# schematic.net
KiCad netlist of a schematic drawn in EasyEDA
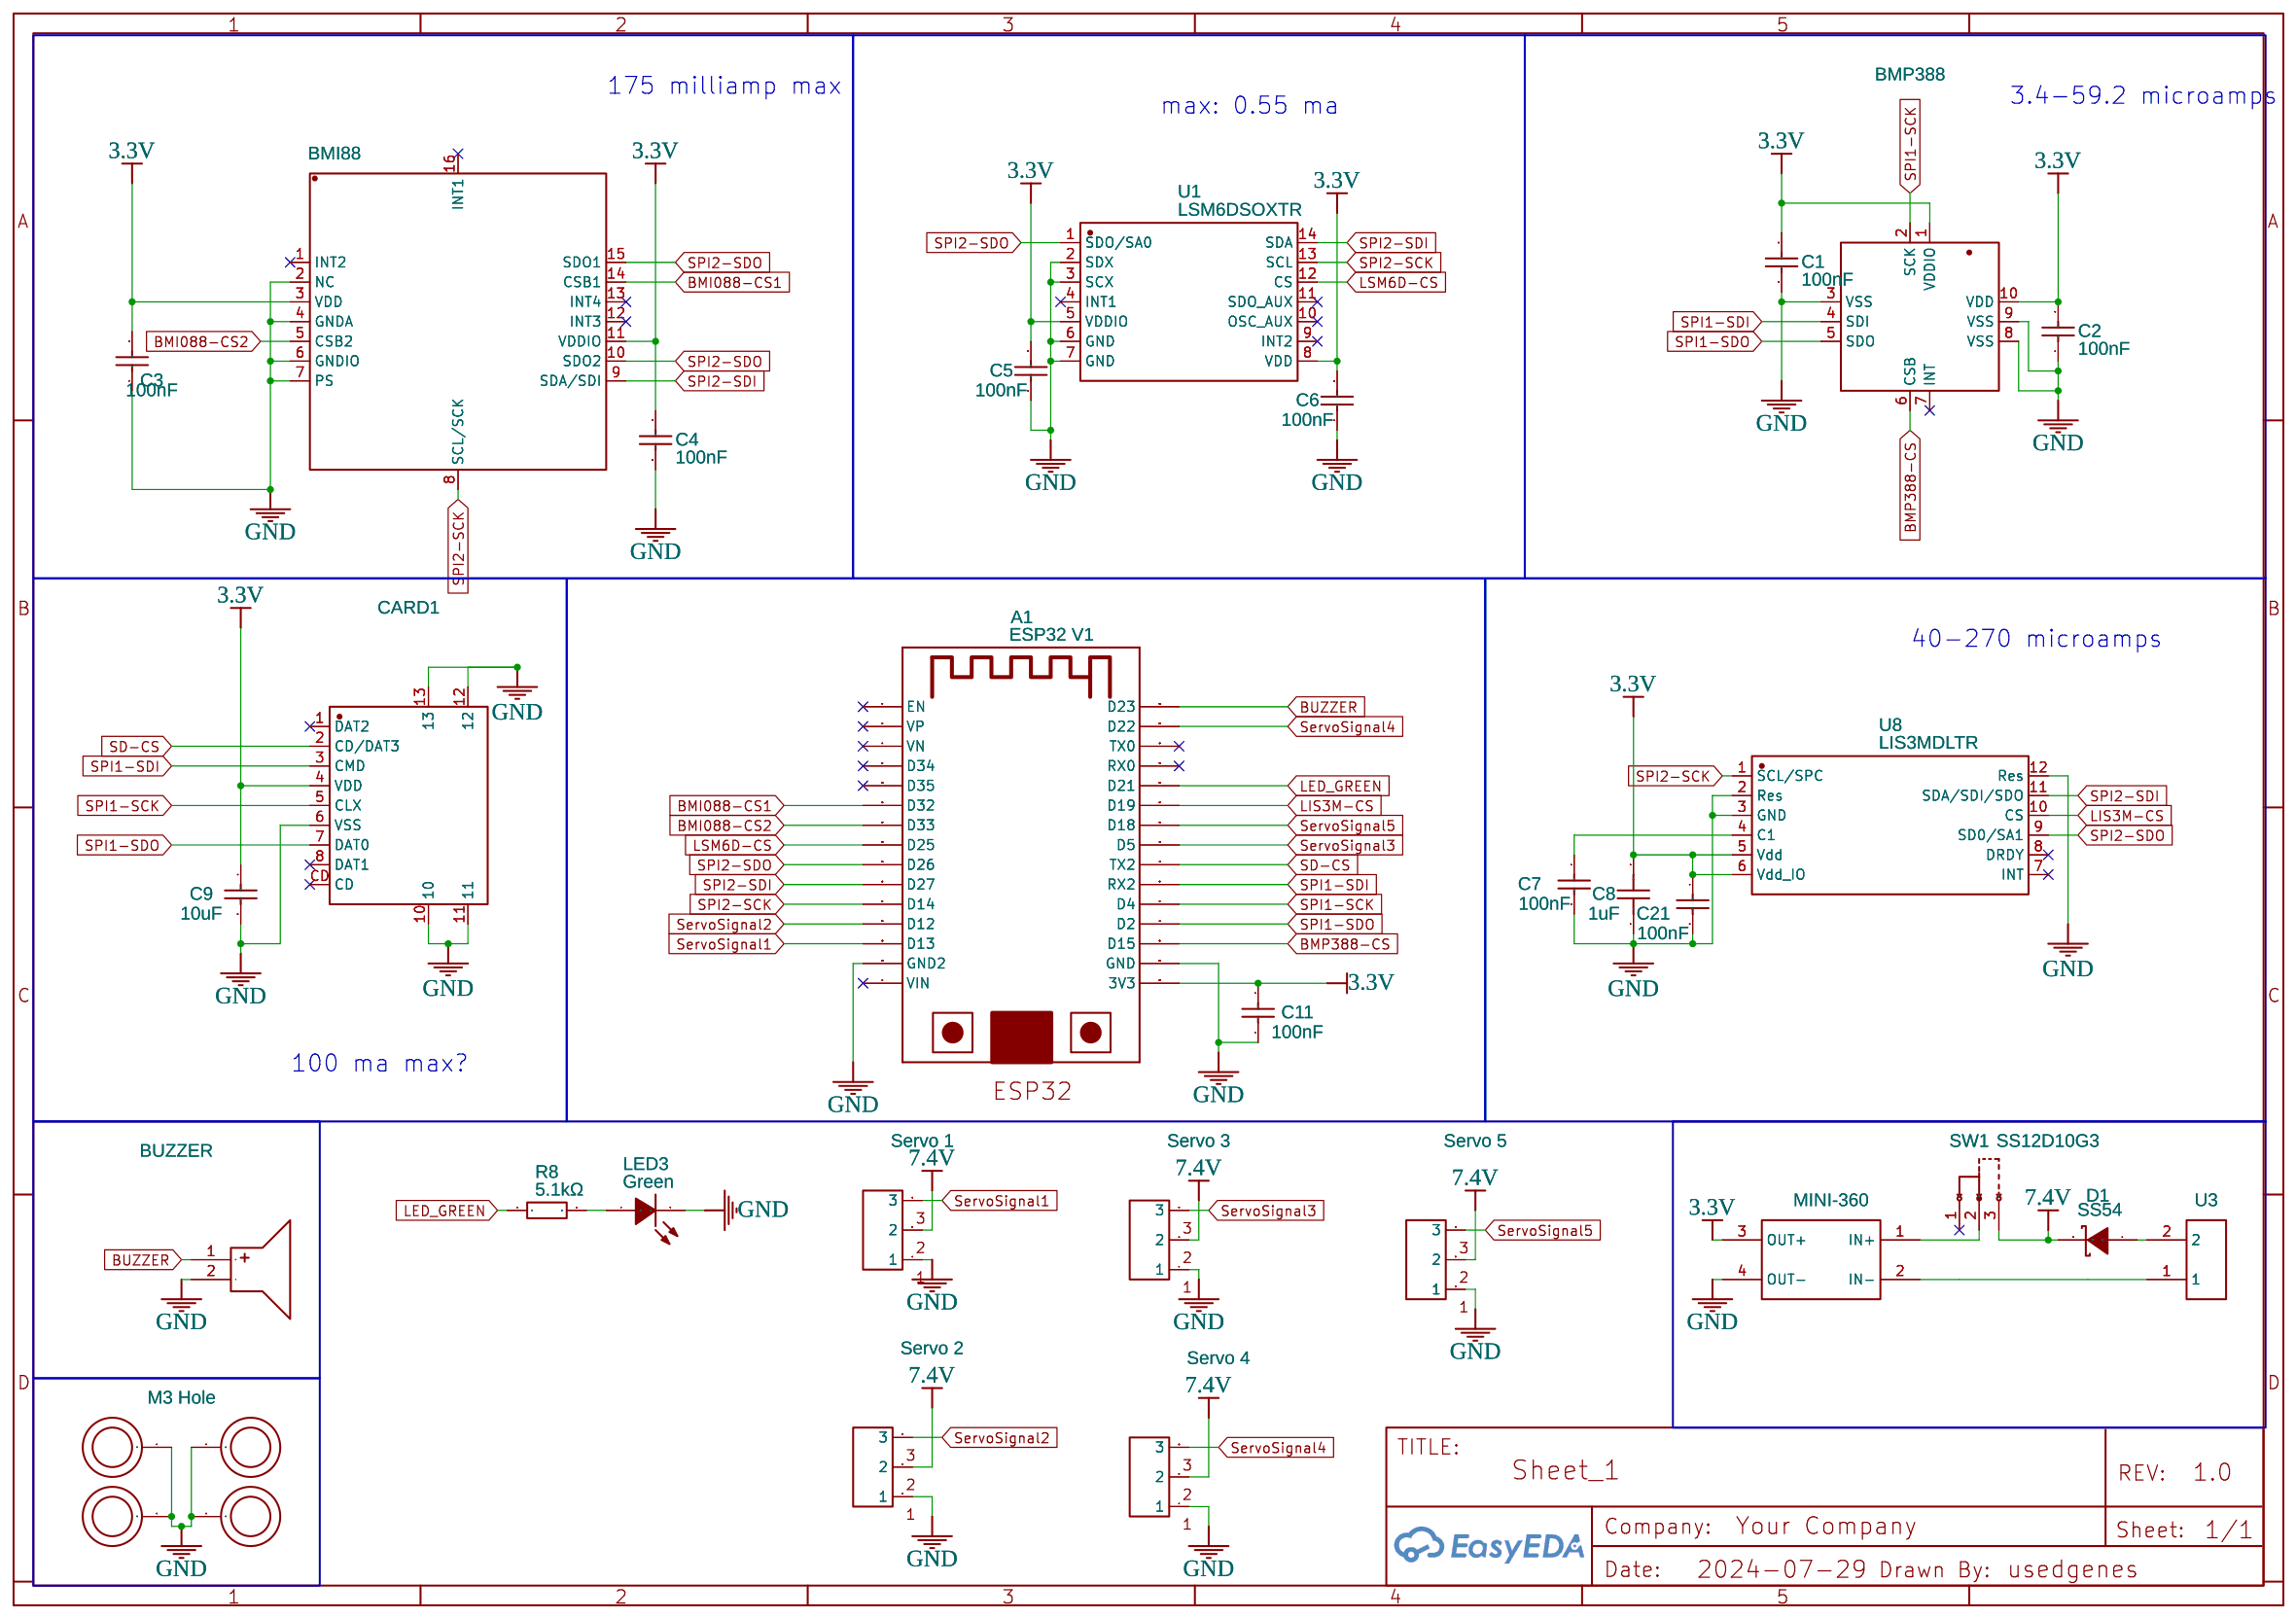
[diagram p0: schematic sheet]

(export (version "E")
  (design (tool "Eeschema 10.0.6"))
  (components
    (comp (ref "A1") (value "ESP32 V1") (libsource (lib "") (part "ESP32-DEVKIT-V1-30PIN")))
    (comp (ref "BMI88")
      (value "BMI088")
      (fields (field (name "Manufacturer") "Bosch(博世)"))
      (libsource (lib "") (part "BMI088"))
    )
    (comp (ref "BMP388")
      (value "BMP388")
      (fields (field (name "Manufacturer") "Bosch(博世)"))
      (libsource (lib "") (part "BMP388"))
    )
    (comp (ref "BUZZER")
      (value "4000Hz")
      (fields
        (field (name "Manufacturer Part") "SKY-1475-0540-45P7.6")
        (field (name "Manufacturer") "S&S(海旭)")
      )
      (libsource (lib "") (part "SKY-1475-0540-45P7.6"))
    )
    (comp (ref "C1")
      (value "100nF")
      (fields
        (field (name "Manufacturer Part") "CL05B104KO5NNNC")
        (field (name "Manufacturer") "SAMSUNG(三星)")
      )
      (libsource (lib "") (part "CL05B104KO5NNNC_1"))
    )
    (comp (ref "C2")
      (value "100nF")
      (fields
        (field (name "Manufacturer Part") "CL05B104KO5NNNC")
        (field (name "Manufacturer") "SAMSUNG(三星)")
      )
      (libsource (lib "") (part "CL05B104KO5NNNC_1"))
    )
    (comp (ref "C3")
      (value "100nF")
      (fields
        (field (name "Manufacturer Part") "CL05B104KO5NNNC")
        (field (name "Manufacturer") "SAMSUNG(三星)")
      )
      (libsource (lib "") (part "CL05B104KO5NNNC_1"))
    )
    (comp (ref "C4")
      (value "100nF")
      (fields
        (field (name "Manufacturer Part") "CL05B104KO5NNNC")
        (field (name "Manufacturer") "SAMSUNG(三星)")
      )
      (libsource (lib "") (part "CL05B104KO5NNNC_1"))
    )
    (comp (ref "C5")
      (value "100nF")
      (fields
        (field (name "Manufacturer Part") "CL05B104KO5NNNC")
        (field (name "Manufacturer") "SAMSUNG(三星)")
      )
      (libsource (lib "") (part "CL05B104KO5NNNC_1"))
    )
    (comp (ref "C6")
      (value "100nF")
      (fields
        (field (name "Manufacturer Part") "CL05B104KO5NNNC")
        (field (name "Manufacturer") "SAMSUNG(三星)")
      )
      (libsource (lib "") (part "CL05B104KO5NNNC_1"))
    )
    (comp (ref "C7")
      (value "100nF")
      (fields
        (field (name "Manufacturer Part") "CL05B104KO5NNNC")
        (field (name "Manufacturer") "SAMSUNG(三星)")
      )
      (libsource (lib "") (part "CL05B104KO5NNNC"))
    )
    (comp (ref "C8")
      (value "1uF")
      (fields
        (field (name "Manufacturer Part") "CL05A105KA5NQNC")
        (field (name "Manufacturer") "SAMSUNG(三星)")
      )
      (libsource (lib "") (part "CL05A105KA5NQNC"))
    )
    (comp (ref "C9")
      (value "10uF")
      (fields
        (field (name "Manufacturer Part") "CL05A106MQ5NUNC")
        (field (name "Manufacturer") "SAMSUNG(三星)")
      )
      (libsource (lib "") (part "CL05A106MQ5NUNC"))
    )
    (comp (ref "C11")
      (value "100nF")
      (fields
        (field (name "Manufacturer Part") "CL05B104KO5NNNC")
        (field (name "Manufacturer") "SAMSUNG(三星)")
      )
      (libsource (lib "") (part "CL05B104KO5NNNC_1"))
    )
    (comp (ref "C21")
      (value "100nF")
      (fields
        (field (name "Manufacturer Part") "CL05B104KO5NNNC")
        (field (name "Manufacturer") "SAMSUNG(三星)")
      )
      (libsource (lib "") (part "CL05B104KO5NNNC"))
    )
    (comp (ref "CARD1")
      (value "TF PUSH")
      (fields (field (name "Manufacturer") "SHOU HAN(首韩)"))
      (libsource (lib "") (part "TF PUSH"))
    )
    (comp (ref "D1")
      (value "SS54")
      (fields (field (name "Manufacturer") "MDD(辰达半导体)"))
      (libsource (lib "") (part "SS54_C22452"))
    )
    (comp (ref "H1") (value "M3 Hole") (libsource (lib "") (part "3MM_HOLE")))
    (comp (ref "H2") (value "3MM_HOLE") (libsource (lib "") (part "3MM_HOLE_1")))
    (comp (ref "H3") (value "3MM_HOLE") (libsource (lib "") (part "3MM_HOLE")))
    (comp (ref "H4") (value "3MM_HOLE") (libsource (lib "") (part "3MM_HOLE_1")))
    (comp (ref "LED3")
      (value "Green")
      (fields (field (name "Manufacturer Part") "KT-0805G") (field (name "Manufacturer") "KENTO"))
      (libsource (lib "") (part "0805G (Green)"))
    )
    (comp (ref "MINI-360") (value "MINI-360") (libsource (lib "") (part "MINI-360")))
    (comp (ref "P1")
      (value "Servo 2")
      (fields
        (field (name "Manufacturer Part") "Female headerHDR1X8-2.54")
        (field (name "Manufacturer") "BOOMELE")
      )
      (libsource (lib "") (part "HEADER PAD 3X RMM COPY"))
    )
    (comp (ref "P2")
      (value "Servo 1")
      (fields
        (field (name "Manufacturer Part") "Female headerHDR1X8-2.54")
        (field (name "Manufacturer") "BOOMELE")
      )
      (libsource (lib "") (part "HEADER PAD 3X RMM COPY"))
    )
    (comp (ref "P3")
      (value "Servo 3")
      (fields
        (field (name "Manufacturer Part") "Female headerHDR1X8-2.54")
        (field (name "Manufacturer") "BOOMELE")
      )
      (libsource (lib "") (part "HEADER PAD 3X RMM COPY"))
    )
    (comp (ref "P4")
      (value "Servo 5")
      (fields
        (field (name "Manufacturer Part") "Female headerHDR1X8-2.54")
        (field (name "Manufacturer") "BOOMELE")
      )
      (libsource (lib "") (part "HEADER PAD 3X RMM COPY"))
    )
    (comp (ref "P5")
      (value "Servo 4")
      (fields
        (field (name "Manufacturer Part") "Female headerHDR1X8-2.54")
        (field (name "Manufacturer") "BOOMELE")
      )
      (libsource (lib "") (part "HEADER PAD 3X RMM COPY"))
    )
    (comp (ref "R8")
      (value "5.1kΩ")
      (fields
        (field (name "Manufacturer Part") "0402WGF5101TCE")
        (field (name "Manufacturer") "UNI-ROYAL(厚声)")
      )
      (libsource (lib "") (part "0402WGF5101TCE"))
    )
    (comp (ref "SW1")
      (value "SS12D10G3")
      (fields (field (name "Manufacturer") "SHOU HAN(首韩)"))
      (libsource (lib "") (part "SS12D10G3"))
    )
    (comp (ref "U1")
      (value "LSM6DSOXTR")
      (fields (field (name "Manufacturer") "ST(意法半导体)"))
      (libsource (lib "") (part "LSM6DSOXTR"))
    )
    (comp (ref "U3") (value "Power Pins") (libsource (lib "") (part "1X2")))
    (comp (ref "U8")
      (value "LIS3MDLTR")
      (fields (field (name "Manufacturer") "ST(意法半导体)"))
      (libsource (lib "") (part "LIS3MDLTR"))
    )
  )
  (nets
    (net (code "1") (name "3.3V") (class "Default")
      (node (ref "A1") (pin "3V3") (pinfunction "3V3_3V3") (pintype "unspecified"))
      (node (ref "BMI88") (pin "11") (pinfunction "VDDIO_11") (pintype "unspecified"))
      (node (ref "BMI88") (pin "3") (pinfunction "VDD_3") (pintype "unspecified"))
      (node (ref "BMP388") (pin "1") (pinfunction "VDDIO_1") (pintype "unspecified"))
      (node (ref "BMP388") (pin "10") (pinfunction "VDD_10") (pintype "unspecified"))
      (node (ref "C1") (pin "2") (pinfunction "2_2") (pintype "input"))
      (node (ref "C11") (pin "2") (pinfunction "2_2") (pintype "input"))
      (node (ref "C2") (pin "2") (pinfunction "2_2") (pintype "input"))
      (node (ref "C21") (pin "1") (pinfunction "1_1") (pintype "input"))
      (node (ref "C3") (pin "2") (pinfunction "2_2") (pintype "input"))
      (node (ref "C4") (pin "2") (pinfunction "2_2") (pintype "input"))
      (node (ref "C5") (pin "2") (pinfunction "2_2") (pintype "input"))
      (node (ref "C6") (pin "2") (pinfunction "2_2") (pintype "input"))
      (node (ref "C8") (pin "2") (pinfunction "2_2") (pintype "unspecified"))
      (node (ref "C9") (pin "1") (pinfunction "1_1") (pintype "input"))
      (node (ref "CARD1") (pin "4") (pinfunction "VDD_4") (pintype "unspecified"))
      (node (ref "MINI-360") (pin "3") (pinfunction "OUT+_3") (pintype "unspecified"))
      (node (ref "U1") (pin "5") (pinfunction "VDDIO_5") (pintype "unspecified"))
      (node (ref "U1") (pin "8") (pinfunction "VDD_8") (pintype "unspecified"))
      (node (ref "U8") (pin "5") (pinfunction "Vdd_5") (pintype "unspecified"))
      (node (ref "U8") (pin "6") (pinfunction "Vdd_IO_6") (pintype "unspecified"))
    )
    (net (code "2") (name "7.4V") (class "Default")
      (node (ref "D1") (pin "2") (pinfunction "K_2") (pintype "unspecified"))
      (node (ref "P1") (pin "2") (pinfunction "2_2") (pintype "unspecified"))
      (node (ref "P2") (pin "2") (pinfunction "2_2") (pintype "unspecified"))
      (node (ref "P3") (pin "2") (pinfunction "2_2") (pintype "unspecified"))
      (node (ref "P4") (pin "2") (pinfunction "2_2") (pintype "unspecified"))
      (node (ref "P5") (pin "2") (pinfunction "2_2") (pintype "unspecified"))
      (node (ref "SW1") (pin "3") (pinfunction "3_3") (pintype "unspecified"))
    )
    (net (code "3") (name "BMI088-CS1") (class "Default")
      (node (ref "A1") (pin "D32") (pinfunction "D32_D32") (pintype "unspecified"))
      (node (ref "BMI88") (pin "14") (pinfunction "CSB1_14") (pintype "unspecified"))
    )
    (net (code "4") (name "BMI088-CS2") (class "Default")
      (node (ref "A1") (pin "D33") (pinfunction "D33_D33") (pintype "unspecified"))
      (node (ref "BMI88") (pin "5") (pinfunction "CSB2_5") (pintype "unspecified"))
    )
    (net (code "5") (name "BMP388-CS") (class "Default")
      (node (ref "A1") (pin "D15") (pinfunction "D15_D15") (pintype "unspecified"))
      (node (ref "BMP388") (pin "6") (pinfunction "CSB_6") (pintype "unspecified"))
    )
    (net (code "6") (name "BUZZER") (class "Default")
      (node (ref "A1") (pin "D23") (pinfunction "D23_D23") (pintype "unspecified"))
      (node (ref "BUZZER") (pin "1") (pinfunction "+_1") (pintype "unspecified"))
    )
    (net (code "7") (name "GND") (class "Default")
      (node (ref "A1") (pin "GND") (pinfunction "GND_GND") (pintype "unspecified"))
      (node (ref "A1") (pin "GND2") (pinfunction "GND2_GND2") (pintype "unspecified"))
      (node (ref "BMI88") (pin "2") (pinfunction "NC_2") (pintype "unspecified"))
      (node (ref "BMI88") (pin "4") (pinfunction "GNDA_4") (pintype "unspecified"))
      (node (ref "BMI88") (pin "6") (pinfunction "GNDIO_6") (pintype "unspecified"))
      (node (ref "BMI88") (pin "7") (pinfunction "PS_7") (pintype "unspecified"))
      (node (ref "BMP388") (pin "3") (pinfunction "VSS_3") (pintype "unspecified"))
      (node (ref "BMP388") (pin "8") (pinfunction "VSS_8") (pintype "unspecified"))
      (node (ref "BMP388") (pin "9") (pinfunction "VSS_9") (pintype "unspecified"))
      (node (ref "BUZZER") (pin "2") (pinfunction "-_2") (pintype "unspecified"))
      (node (ref "C1") (pin "1") (pinfunction "1_1") (pintype "input"))
      (node (ref "C11") (pin "1") (pinfunction "1_1") (pintype "input"))
      (node (ref "C2") (pin "1") (pinfunction "1_1") (pintype "input"))
      (node (ref "C21") (pin "2") (pinfunction "2_2") (pintype "input"))
      (node (ref "C3") (pin "1") (pinfunction "1_1") (pintype "input"))
      (node (ref "C4") (pin "1") (pinfunction "1_1") (pintype "input"))
      (node (ref "C5") (pin "1") (pinfunction "1_1") (pintype "input"))
      (node (ref "C6") (pin "1") (pinfunction "1_1") (pintype "input"))
      (node (ref "C7") (pin "2") (pinfunction "2_2") (pintype "input"))
      (node (ref "C8") (pin "1") (pinfunction "1_1") (pintype "unspecified"))
      (node (ref "C9") (pin "2") (pinfunction "2_2") (pintype "input"))
      (node (ref "CARD1") (pin "10") (pinfunction "10_10") (pintype "unspecified"))
      (node (ref "CARD1") (pin "11") (pinfunction "11_11") (pintype "unspecified"))
      (node (ref "CARD1") (pin "12") (pinfunction "12_12") (pintype "unspecified"))
      (node (ref "CARD1") (pin "13") (pinfunction "13_13") (pintype "unspecified"))
      (node (ref "CARD1") (pin "6") (pinfunction "VSS_6") (pintype "unspecified"))
      (node (ref "H1") (pin "1") (pinfunction "1_1") (pintype "bidirectional"))
      (node (ref "H2") (pin "1") (pinfunction "1_1") (pintype "bidirectional"))
      (node (ref "H3") (pin "1") (pinfunction "1_1") (pintype "bidirectional"))
      (node (ref "H4") (pin "1") (pinfunction "1_1") (pintype "bidirectional"))
      (node (ref "LED3") (pin "2") (pinfunction "K_2") (pintype "unspecified"))
      (node (ref "MINI-360") (pin "4") (pinfunction "OUT-_4") (pintype "unspecified"))
      (node (ref "P1") (pin "1") (pinfunction "1_1") (pintype "unspecified"))
      (node (ref "P2") (pin "1") (pinfunction "1_1") (pintype "unspecified"))
      (node (ref "P3") (pin "1") (pinfunction "1_1") (pintype "unspecified"))
      (node (ref "P4") (pin "1") (pinfunction "1_1") (pintype "unspecified"))
      (node (ref "P5") (pin "1") (pinfunction "1_1") (pintype "unspecified"))
      (node (ref "U1") (pin "2") (pinfunction "SDX_2") (pintype "unspecified"))
      (node (ref "U1") (pin "3") (pinfunction "SCX_3") (pintype "unspecified"))
      (node (ref "U1") (pin "6") (pinfunction "GND_6") (pintype "unspecified"))
      (node (ref "U1") (pin "7") (pinfunction "GND_7") (pintype "unspecified"))
      (node (ref "U8") (pin "12") (pinfunction "Res_12") (pintype "unspecified"))
      (node (ref "U8") (pin "2") (pinfunction "Res_2") (pintype "unspecified"))
      (node (ref "U8") (pin "3") (pinfunction "GND_3") (pintype "unspecified"))
    )
    (net (code "8") (name "LED_GREEN") (class "Default")
      (node (ref "A1") (pin "D21") (pinfunction "D21_D21") (pintype "unspecified"))
      (node (ref "R8") (pin "1") (pinfunction "1_1") (pintype "input"))
    )
    (net (code "9") (name "LIS3M-CS") (class "Default")
      (node (ref "A1") (pin "D19") (pinfunction "D19_D19") (pintype "unspecified"))
      (node (ref "U8") (pin "10") (pinfunction "CS_10") (pintype "unspecified"))
    )
    (net (code "10") (name "LSM6D-CS") (class "Default")
      (node (ref "A1") (pin "D25") (pinfunction "D25_D25") (pintype "unspecified"))
      (node (ref "U1") (pin "12") (pinfunction "CS_12") (pintype "unspecified"))
    )
    (net (code "11") (name "Net-(D1-A)") (class "Default")
      (node (ref "D1") (pin "1") (pinfunction "A_1") (pintype "unspecified"))
      (node (ref "U3") (pin "2") (pinfunction "2_2") (pintype "unspecified"))
    )
    (net (code "12") (name "Net-(LED3-A)") (class "Default")
      (node (ref "LED3") (pin "1") (pinfunction "A_1") (pintype "unspecified"))
      (node (ref "R8") (pin "2") (pinfunction "2_2") (pintype "input"))
    )
    (net (code "13") (name "Net-(MINI-360-IN+)") (class "Default")
      (node (ref "MINI-360") (pin "1") (pinfunction "IN+_1") (pintype "unspecified"))
      (node (ref "SW1") (pin "2") (pinfunction "2_2") (pintype "unspecified"))
    )
    (net (code "14") (name "Net-(MINI-360-IN-)") (class "Default")
      (node (ref "MINI-360") (pin "2") (pinfunction "IN-_2") (pintype "unspecified"))
      (node (ref "U3") (pin "1") (pinfunction "1_1") (pintype "unspecified"))
    )
    (net (code "15") (name "Net-(U8-C1)") (class "Default")
      (node (ref "C7") (pin "1") (pinfunction "1_1") (pintype "input"))
      (node (ref "U8") (pin "4") (pinfunction "C1_4") (pintype "unspecified"))
    )
    (net (code "16") (name "SD-CS") (class "Default")
      (node (ref "A1") (pin "TX2") (pinfunction "TX2_TX2") (pintype "unspecified"))
      (node (ref "CARD1") (pin "2") (pinfunction "CD/DAT3_2") (pintype "unspecified"))
    )
    (net (code "17") (name "SPI1-SCK") (class "Default")
      (node (ref "A1") (pin "D4") (pinfunction "D4_D4") (pintype "unspecified"))
      (node (ref "BMP388") (pin "2") (pinfunction "SCK_2") (pintype "unspecified"))
      (node (ref "CARD1") (pin "5") (pinfunction "CLX_5") (pintype "unspecified"))
    )
    (net (code "18") (name "SPI1-SDI") (class "Default")
      (node (ref "A1") (pin "RX2") (pinfunction "RX2_RX2") (pintype "unspecified"))
      (node (ref "BMP388") (pin "4") (pinfunction "SDI_4") (pintype "unspecified"))
      (node (ref "CARD1") (pin "3") (pinfunction "CMD_3") (pintype "unspecified"))
    )
    (net (code "19") (name "SPI1-SDO") (class "Default")
      (node (ref "A1") (pin "D2") (pinfunction "D2_D2") (pintype "unspecified"))
      (node (ref "BMP388") (pin "5") (pinfunction "SDO_5") (pintype "unspecified"))
      (node (ref "CARD1") (pin "7") (pinfunction "DAT0_7") (pintype "unspecified"))
    )
    (net (code "20") (name "SPI2-SCK") (class "Default")
      (node (ref "A1") (pin "D14") (pinfunction "D14_D14") (pintype "unspecified"))
      (node (ref "BMI88") (pin "8") (pinfunction "SCL/SCK_8") (pintype "unspecified"))
      (node (ref "U1") (pin "13") (pinfunction "SCL_13") (pintype "unspecified"))
      (node (ref "U8") (pin "1") (pinfunction "SCL/SPC_1") (pintype "unspecified"))
    )
    (net (code "21") (name "SPI2-SDI") (class "Default")
      (node (ref "A1") (pin "D27") (pinfunction "D27_D27") (pintype "unspecified"))
      (node (ref "BMI88") (pin "9") (pinfunction "SDA/SDI_9") (pintype "unspecified"))
      (node (ref "U1") (pin "14") (pinfunction "SDA_14") (pintype "unspecified"))
      (node (ref "U8") (pin "11") (pinfunction "SDA/SDI/SDO_11") (pintype "unspecified"))
    )
    (net (code "22") (name "SPI2-SDO") (class "Default")
      (node (ref "A1") (pin "D26") (pinfunction "D26_D26") (pintype "unspecified"))
      (node (ref "BMI88") (pin "10") (pinfunction "SDO2_10") (pintype "unspecified"))
      (node (ref "BMI88") (pin "15") (pinfunction "SDO1_15") (pintype "unspecified"))
      (node (ref "U1") (pin "1") (pinfunction "SDO/SA0_1") (pintype "unspecified"))
      (node (ref "U8") (pin "9") (pinfunction "SD0/SA1_9") (pintype "unspecified"))
    )
    (net (code "23") (name "ServoSignal1") (class "Default")
      (node (ref "A1") (pin "D13") (pinfunction "D13_D13") (pintype "unspecified"))
      (node (ref "P2") (pin "3") (pinfunction "3_3") (pintype "unspecified"))
    )
    (net (code "24") (name "ServoSignal2") (class "Default")
      (node (ref "A1") (pin "D12") (pinfunction "D12_D12") (pintype "unspecified"))
      (node (ref "P1") (pin "3") (pinfunction "3_3") (pintype "unspecified"))
    )
    (net (code "25") (name "ServoSignal3") (class "Default")
      (node (ref "A1") (pin "D5") (pinfunction "D5_D5") (pintype "unspecified"))
      (node (ref "P3") (pin "3") (pinfunction "3_3") (pintype "unspecified"))
    )
    (net (code "26") (name "ServoSignal4") (class "Default")
      (node (ref "A1") (pin "D22") (pinfunction "D22_D22") (pintype "unspecified"))
      (node (ref "P5") (pin "3") (pinfunction "3_3") (pintype "unspecified"))
    )
    (net (code "27") (name "ServoSignal5") (class "Default")
      (node (ref "A1") (pin "D18") (pinfunction "D18_D18") (pintype "unspecified"))
      (node (ref "P4") (pin "3") (pinfunction "3_3") (pintype "unspecified"))
    )
    (net (code "28") (name "unconnected-(A1-PadD34)") (class "Default")
      (node (ref "A1") (pin "D34") (pinfunction "D34_D34") (pintype "unspecified+no_connect"))
    )
    (net (code "29") (name "unconnected-(A1-PadD35)") (class "Default")
      (node (ref "A1") (pin "D35") (pinfunction "D35_D35") (pintype "unspecified+no_connect"))
    )
    (net (code "30") (name "unconnected-(A1-PadEN)") (class "Default")
      (node (ref "A1") (pin "EN") (pinfunction "EN_EN") (pintype "unspecified+no_connect"))
    )
    (net (code "31") (name "unconnected-(A1-PadRX0)") (class "Default")
      (node (ref "A1") (pin "RX0") (pinfunction "RX0_RX0") (pintype "unspecified+no_connect"))
    )
    (net (code "32") (name "unconnected-(A1-PadTX0)") (class "Default")
      (node (ref "A1") (pin "TX0") (pinfunction "TX0_TX0") (pintype "unspecified+no_connect"))
    )
    (net (code "33") (name "unconnected-(A1-PadVIN)") (class "Default")
      (node (ref "A1") (pin "VIN") (pinfunction "VIN_VIN") (pintype "unspecified+no_connect"))
    )
    (net (code "34") (name "unconnected-(A1-PadVN)") (class "Default")
      (node (ref "A1") (pin "VN") (pinfunction "VN_VN") (pintype "unspecified+no_connect"))
    )
    (net (code "35") (name "unconnected-(A1-PadVP)") (class "Default")
      (node (ref "A1") (pin "VP") (pinfunction "VP_VP") (pintype "unspecified+no_connect"))
    )
    (net (code "36") (name "unconnected-(BMI88-INT1-Pad16)") (class "Default")
      (node (ref "BMI88") (pin "16") (pinfunction "INT1_16") (pintype "unspecified+no_connect"))
    )
    (net (code "37") (name "unconnected-(BMI88-INT2-Pad1)") (class "Default")
      (node (ref "BMI88") (pin "1") (pinfunction "INT2_1") (pintype "unspecified+no_connect"))
    )
    (net (code "38") (name "unconnected-(BMI88-INT3-Pad12)") (class "Default")
      (node (ref "BMI88") (pin "12") (pinfunction "INT3_12") (pintype "unspecified+no_connect"))
    )
    (net (code "39") (name "unconnected-(BMI88-INT4-Pad13)") (class "Default")
      (node (ref "BMI88") (pin "13") (pinfunction "INT4_13") (pintype "unspecified+no_connect"))
    )
    (net (code "40") (name "unconnected-(BMP388-INT-Pad7)") (class "Default")
      (node (ref "BMP388") (pin "7") (pinfunction "INT_7") (pintype "unspecified+no_connect"))
    )
    (net (code "41") (name "unconnected-(CARD1-DAT1-Pad8)") (class "Default")
      (node (ref "CARD1") (pin "8") (pinfunction "DAT1_8") (pintype "unspecified+no_connect"))
    )
    (net (code "42") (name "unconnected-(CARD1-DAT2-Pad1)") (class "Default")
      (node (ref "CARD1") (pin "1") (pinfunction "DAT2_1") (pintype "unspecified+no_connect"))
    )
    (net (code "43") (name "unconnected-(CARD1-PadCD)") (class "Default")
      (node (ref "CARD1") (pin "CD") (pinfunction "CD_CD") (pintype "unspecified+no_connect"))
    )
    (net (code "44") (name "unconnected-(SW1-Pad1)") (class "Default")
      (node (ref "SW1") (pin "1") (pinfunction "1_1") (pintype "unspecified+no_connect"))
    )
    (net (code "45") (name "unconnected-(U1-INT1-Pad4)") (class "Default")
      (node (ref "U1") (pin "4") (pinfunction "INT1_4") (pintype "unspecified+no_connect"))
    )
    (net (code "46") (name "unconnected-(U1-INT2-Pad9)") (class "Default")
      (node (ref "U1") (pin "9") (pinfunction "INT2_9") (pintype "unspecified+no_connect"))
    )
    (net (code "47") (name "unconnected-(U1-OSC_AUX-Pad10)") (class "Default")
      (node (ref "U1") (pin "10") (pinfunction "OSC_AUX_10") (pintype "unspecified+no_connect"))
    )
    (net (code "48") (name "unconnected-(U1-SDO_AUX-Pad11)") (class "Default")
      (node (ref "U1") (pin "11") (pinfunction "SDO_AUX_11") (pintype "unspecified+no_connect"))
    )
    (net (code "49") (name "unconnected-(U8-DRDY-Pad8)") (class "Default")
      (node (ref "U8") (pin "8") (pinfunction "DRDY_8") (pintype "unspecified+no_connect"))
    )
    (net (code "50") (name "unconnected-(U8-INT-Pad7)") (class "Default")
      (node (ref "U8") (pin "7") (pinfunction "INT_7") (pintype "unspecified+no_connect"))
    )
  )
)
